# 2_input_v1.net
KiCad netlist of a schematic drawn in EAGLE
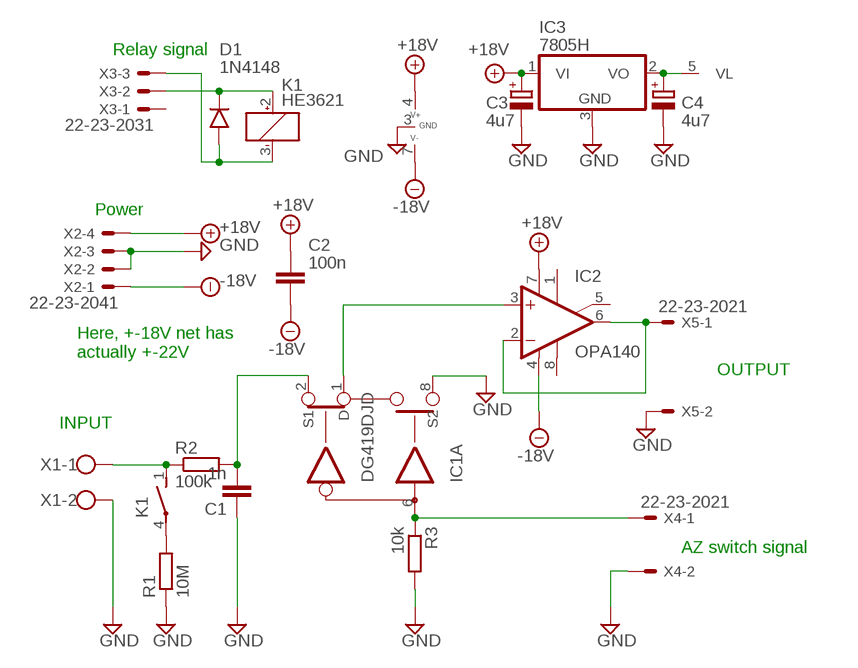
[diagram p0: schematic, sheet 1]

(export (version "E")
  (design (tool "Eeschema 10.0.6"))
  (components
    (comp (ref "C1")
      (value "1n")
      (footprint "eagle-import:C050-025X075")
      (libsource (lib "eagle-import") (part "C-EU050-025X075"))
    )
    (comp (ref "C2")
      (value "100n")
      (footprint "eagle-import:C025-025X050")
      (libsource (lib "eagle-import") (part "C-EU025-025X050"))
    )
    (comp (ref "C3")
      (value "4u7")
      (footprint "eagle-import:E2,5-5")
      (libsource (lib "eagle-import") (part "CPOL-EUE2.5-5"))
    )
    (comp (ref "C4")
      (value "4u7")
      (footprint "eagle-import:E2,5-5")
      (libsource (lib "eagle-import") (part "CPOL-EUE2.5-5"))
    )
    (comp (ref "D1")
      (value "1N4148")
      (footprint "eagle-import:SOD-80")
      (libsource (lib "eagle-import") (part "1N4148SOD"))
    )
    (comp (ref "IC1")
      (value "DG419DJD")
      (footprint "eagle-import:SO08")
      (libsource (lib "eagle-import") (part "DG419DJD"))
    )
    (comp (ref "IC2")
      (value "OPA140")
      (footprint "eagle-import:SO08")
      (libsource (lib "eagle-import") (part "TL071D"))
    )
    (comp (ref "IC3")
      (value "7805H")
      (footprint "eagle-import:TO39")
      (libsource (lib "eagle-import") (part "78H05"))
    )
    (comp (ref "K1")
      (value "HE3621")
      (footprint "eagle-import:HE3621")
      (libsource (lib "eagle-import") (part "HE3621"))
    )
    (comp (ref "R1")
      (value "10M")
      (footprint "eagle-import:R_TR193")
      (libsource (lib "eagle-import") (part "R193"))
    )
    (comp (ref "R2")
      (value "100k")
      (footprint "eagle-import:R_TR192")
      (libsource (lib "eagle-import") (part "R192"))
    )
    (comp (ref "R3")
      (value "10k")
      (footprint "eagle-import:R_TR191")
      (libsource (lib "eagle-import") (part "R191"))
    )
    (comp (ref "X1")
      (value "W237-2N")
      (footprint "eagle-import:W237-2N")
      (libsource (lib "eagle-import") (part "W237-2N"))
    )
    (comp (ref "X2")
      (value "22-23-2041")
      (footprint "eagle-import:22-23-2041")
      (fields (field (name "MF") "MOLEX"))
      (libsource (lib "eagle-import") (part "22-23-2041"))
    )
    (comp (ref "X3")
      (value "22-23-2031")
      (footprint "eagle-import:22-23-2031")
      (fields (field (name "MF") "MOLEX"))
      (libsource (lib "eagle-import") (part "22-23-2031"))
    )
    (comp (ref "X4")
      (value "22-23-2021")
      (footprint "eagle-import:22-23-2021")
      (fields (field (name "MF") "MOLEX"))
      (libsource (lib "eagle-import") (part "22-23-2021"))
    )
    (comp (ref "X5")
      (value "22-23-2021")
      (footprint "eagle-import:22-23-2021")
      (fields (field (name "MF") "MOLEX"))
      (libsource (lib "eagle-import") (part "22-23-2021"))
    )
  )
  (nets
    (net (code "1") (name "+18V") (class "Default")
      (node (ref "C2") (pin "1") (pinfunction "1_1") (pintype "passive"))
      (node (ref "C3") (pin "+") (pinfunction "+_+") (pintype "passive"))
      (node (ref "IC1") (pin "4") (pinfunction "V+_4") (pintype "power_in"))
      (node (ref "IC2") (pin "7") (pinfunction "V+_7") (pintype "power_in"))
      (node (ref "IC3") (pin "1") (pinfunction "VI_1") (pintype "input"))
      (node (ref "X2") (pin "4") (pinfunction "S_4") (pintype "passive"))
    )
    (net (code "2") (name "-18V") (class "Default")
      (node (ref "C2") (pin "2") (pinfunction "2_2") (pintype "passive"))
      (node (ref "IC1") (pin "7") (pinfunction "V-_7") (pintype "power_in"))
      (node (ref "IC2") (pin "4") (pinfunction "V-_4") (pintype "power_in"))
      (node (ref "X2") (pin "1") (pinfunction "S_1") (pintype "passive"))
    )
    (net (code "3") (name "GND") (class "Default")
      (node (ref "C1") (pin "1") (pinfunction "1_1") (pintype "passive"))
      (node (ref "C3") (pin "-") (pinfunction "-_-") (pintype "passive"))
      (node (ref "C4") (pin "-") (pinfunction "-_-") (pintype "passive"))
      (node (ref "IC1") (pin "3") (pinfunction "GND_3") (pintype "power_in"))
      (node (ref "IC1") (pin "8") (pinfunction "S2_8") (pintype "bidirectional"))
      (node (ref "IC3") (pin "3") (pinfunction "GND_3") (pintype "passive"))
      (node (ref "R1") (pin "P$1") (pinfunction "1_P$1") (pintype "passive"))
      (node (ref "R3") (pin "P$2") (pinfunction "2_P$2") (pintype "passive"))
      (node (ref "X1") (pin "2") (pinfunction "KL_2") (pintype "passive"))
      (node (ref "X2") (pin "2") (pinfunction "S_2") (pintype "passive"))
      (node (ref "X2") (pin "3") (pinfunction "S_3") (pintype "passive"))
      (node (ref "X4") (pin "2") (pinfunction "S_2") (pintype "passive"))
      (node (ref "X5") (pin "2") (pinfunction "S_2") (pintype "passive"))
    )
    (net (code "4") (name "Net-(IC1A-D)") (class "Default")
      (node (ref "IC1") (pin "1") (pinfunction "D_1") (pintype "bidirectional"))
      (node (ref "IC2") (pin "3") (pinfunction "+IN_3") (pintype "input"))
    )
    (net (code "5") (name "Net-(IC1A-IN)") (class "Default")
      (node (ref "IC1") (pin "6") (pinfunction "IN_6") (pintype "input"))
      (node (ref "R3") (pin "P$1") (pinfunction "1_P$1") (pintype "passive"))
      (node (ref "X4") (pin "1") (pinfunction "S_1") (pintype "passive"))
    )
    (net (code "6") (name "Net-(IC1A-S1)") (class "Default")
      (node (ref "C1") (pin "2") (pinfunction "2_2") (pintype "passive"))
      (node (ref "IC1") (pin "2") (pinfunction "S1_2") (pintype "bidirectional"))
      (node (ref "R2") (pin "P$2") (pinfunction "2_P$2") (pintype "passive"))
    )
    (net (code "7") (name "Net-(IC1C-VL)") (class "Default")
      (node (ref "C4") (pin "+") (pinfunction "+_+") (pintype "passive"))
      (node (ref "IC1") (pin "5") (pinfunction "VL_5") (pintype "input"))
      (node (ref "IC3") (pin "2") (pinfunction "VO_2") (pintype "passive"))
    )
    (net (code "8") (name "Net-(IC2--IN)") (class "Default")
      (node (ref "IC2") (pin "2") (pinfunction "-IN_2") (pintype "input"))
      (node (ref "IC2") (pin "6") (pinfunction "OUT_6") (pintype "output"))
      (node (ref "X5") (pin "1") (pinfunction "S_1") (pintype "passive"))
    )
    (net (code "9") (name "Net-(K1A-+)") (class "Default")
      (node (ref "D1") (pin "K") (pinfunction "K_K") (pintype "output"))
      (node (ref "K1") (pin "2") (pinfunction "+_2") (pintype "passive"))
      (node (ref "X3") (pin "2") (pinfunction "S_2") (pintype "passive"))
    )
    (net (code "10") (name "Net-(K1A--)") (class "Default")
      (node (ref "D1") (pin "A") (pinfunction "A_A") (pintype "input"))
      (node (ref "K1") (pin "3") (pinfunction "-_3") (pintype "passive"))
      (node (ref "X3") (pin "3") (pinfunction "S_3") (pintype "passive"))
    )
    (net (code "11") (name "Net-(K1B-P)") (class "Default")
      (node (ref "K1") (pin "4") (pinfunction "P_4") (pintype "passive"))
      (node (ref "R1") (pin "P$2") (pinfunction "2_P$2") (pintype "passive"))
    )
    (net (code "12") (name "Net-(K1B-S)") (class "Default")
      (node (ref "K1") (pin "1") (pinfunction "S_1") (pintype "passive"))
      (node (ref "R2") (pin "P$1") (pinfunction "1_P$1") (pintype "passive"))
      (node (ref "X1") (pin "1") (pinfunction "KL_1") (pintype "passive"))
    )
    (net (code "13") (name "unconnected-(IC2-ON1-Pad1)") (class "Default")
      (node (ref "IC2") (pin "1") (pinfunction "ON1_1") (pintype "passive"))
    )
    (net (code "14") (name "unconnected-(IC2-ON2-Pad5)") (class "Default")
      (node (ref "IC2") (pin "5") (pinfunction "ON2_5") (pintype "passive"))
    )
    (net (code "15") (name "unconnected-(IC2-OPT-Pad8)") (class "Default")
      (node (ref "IC2") (pin "8") (pinfunction "OPT_8") (pintype "passive"))
    )
    (net (code "16") (name "unconnected-(X3A-S-Pad1)") (class "Default")
      (node (ref "X3") (pin "1") (pinfunction "S_1") (pintype "passive"))
    )
  )
)
